# ESP32MainSchematice.net
KiCad netlist of a schematic drawn in Altium Designer
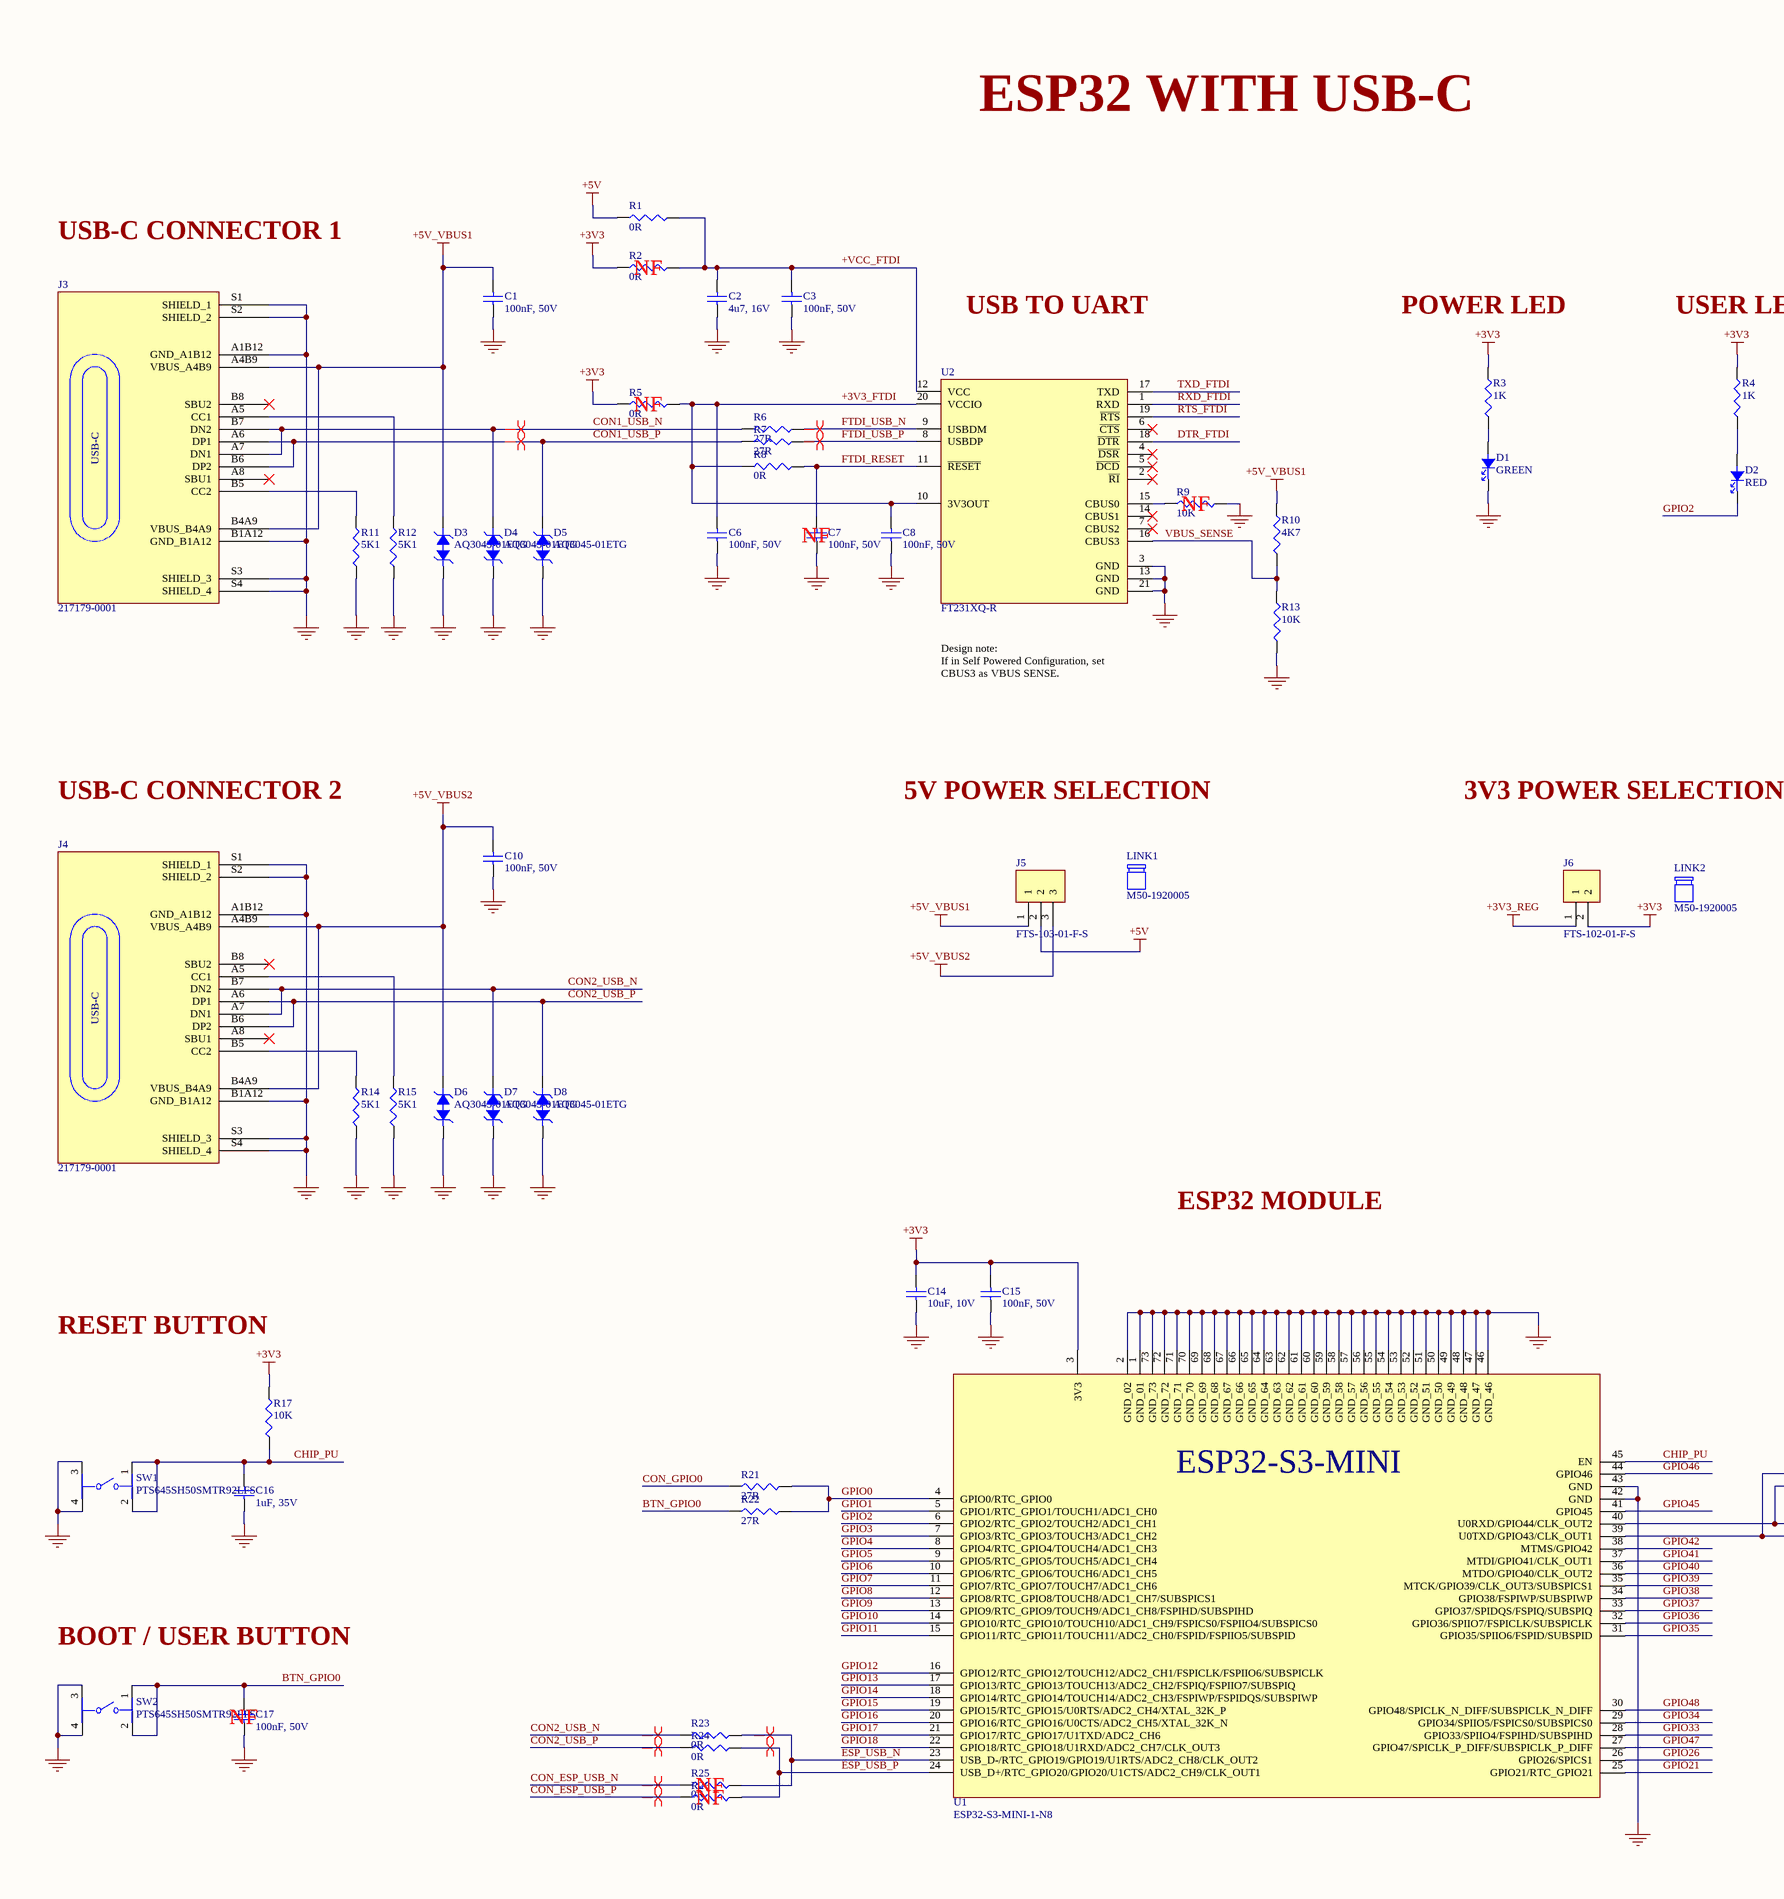
[diagram p0: ESP32MainSchematice.SchDoc, left]
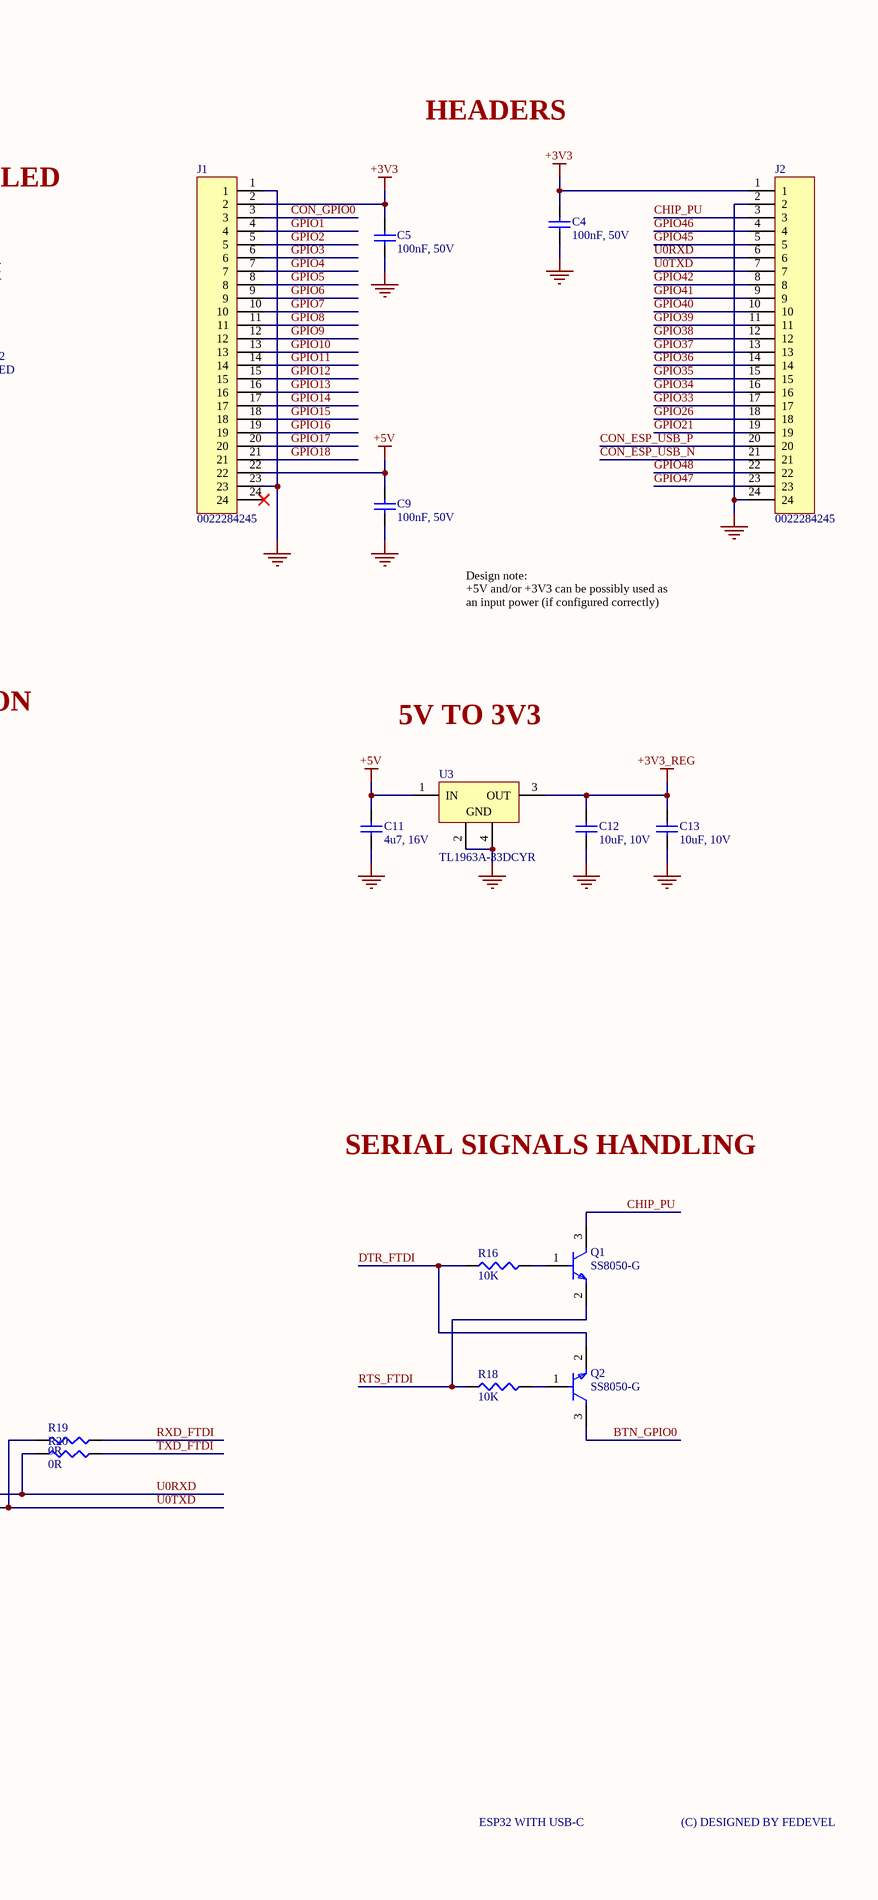
[diagram p1: ESP32MainSchematice.SchDoc, right]

(export (version "E")
  (design (tool "Eeschema 10.0.6"))
  (components
    (comp (ref "C1")
      (value "100nF, 50V")
      (footprint "CAPC1005X55N")
      (description "CAP CER 0.1UF 50V X7R 0402")
      (fields
        (field (name "MANUFACTURER") "Samsung")
        (field (name "MANUFACTURER PART NUMBER") "CL05B104KB54PNC")
      )
      (libsource (lib "Schlib") (part "CL05B104KB54PNC"))
    )
    (comp (ref "C2")
      (value "4u7, 16V")
      (footprint "CAPC1005X55N")
      (description "CAP CER 4.7UF 16V X5R 0402")
      (fields
        (field (name "MANUFACTURER") "Samsung")
        (field (name "MANUFACTURER PART NUMBER") "CL05A475MO5NUNC")
      )
      (libsource (lib "Schlib") (part "CL05A475MO5NUNC"))
    )
    (comp (ref "C3")
      (value "100nF, 50V")
      (footprint "CAPC1005X55N")
      (description "CAP CER 0.1UF 50V X7R 0402")
      (fields
        (field (name "MANUFACTURER") "Samsung")
        (field (name "MANUFACTURER PART NUMBER") "CL05B104KB54PNC")
      )
      (libsource (lib "Schlib") (part "CL05B104KB54PNC"))
    )
    (comp (ref "C4")
      (value "100nF, 50V")
      (footprint "CAPC1005X55N")
      (description "CAP CER 0.1UF 50V X7R 0402")
      (fields
        (field (name "MANUFACTURER") "Samsung")
        (field (name "MANUFACTURER PART NUMBER") "CL05B104KB54PNC")
      )
      (libsource (lib "Schlib") (part "CL05B104KB54PNC"))
    )
    (comp (ref "C5")
      (value "100nF, 50V")
      (footprint "CAPC1005X55N")
      (description "CAP CER 0.1UF 50V X7R 0402")
      (fields
        (field (name "MANUFACTURER") "Samsung")
        (field (name "MANUFACTURER PART NUMBER") "CL05B104KB54PNC")
      )
      (libsource (lib "Schlib") (part "CL05B104KB54PNC"))
    )
    (comp (ref "C6")
      (value "100nF, 50V")
      (footprint "CAPC1005X55N")
      (description "CAP CER 0.1UF 50V X7R 0402")
      (fields
        (field (name "MANUFACTURER") "Samsung")
        (field (name "MANUFACTURER PART NUMBER") "CL05B104KB54PNC")
      )
      (libsource (lib "Schlib") (part "CL05B104KB54PNC"))
    )
    (comp (ref "C7")
      (value "100nF, 50V")
      (footprint "CAPC1005X55N")
      (description "CAP CER 0.1UF 50V X7R 0402")
      (fields
        (field (name "MANUFACTURER") "Samsung")
        (field (name "MANUFACTURER PART NUMBER") "CL05B104KB54PNC")
      )
      (libsource (lib "Schlib") (part "CL05B104KB54PNC"))
    )
    (comp (ref "C8")
      (value "100nF, 50V")
      (footprint "CAPC1005X55N")
      (description "CAP CER 0.1UF 50V X7R 0402")
      (fields
        (field (name "MANUFACTURER") "Samsung")
        (field (name "MANUFACTURER PART NUMBER") "CL05B104KB54PNC")
      )
      (libsource (lib "Schlib") (part "CL05B104KB54PNC"))
    )
    (comp (ref "C9")
      (value "100nF, 50V")
      (footprint "CAPC1005X55N")
      (description "CAP CER 0.1UF 50V X7R 0402")
      (fields
        (field (name "MANUFACTURER") "Samsung")
        (field (name "MANUFACTURER PART NUMBER") "CL05B104KB54PNC")
      )
      (libsource (lib "Schlib") (part "CL05B104KB54PNC"))
    )
    (comp (ref "C10")
      (value "100nF, 50V")
      (footprint "CAPC1005X55N")
      (description "CAP CER 0.1UF 50V X7R 0402")
      (fields
        (field (name "MANUFACTURER") "Samsung")
        (field (name "MANUFACTURER PART NUMBER") "CL05B104KB54PNC")
      )
      (libsource (lib "Schlib") (part "CL05B104KB54PNC"))
    )
    (comp (ref "C11")
      (value "4u7, 16V")
      (footprint "CAPC1005X55N")
      (description "CAP CER 4.7UF 16V X5R 0402")
      (fields
        (field (name "MANUFACTURER") "Samsung")
        (field (name "MANUFACTURER PART NUMBER") "CL05A475MO5NUNC")
      )
      (libsource (lib "Schlib") (part "CL05A475MO5NUNC"))
    )
    (comp (ref "C12")
      (value "10uF, 10V")
      (footprint "CAPC1005X55N")
      (description "CAP CER 10UF 10V X5R 0402")
      (fields
        (field (name "MANUFACTURER") "Samsung")
        (field (name "MANUFACTURER PART NUMBER") "CL05A106MP8NUB8")
      )
      (libsource (lib "Schlib") (part "CL05A106MP8NUB8"))
    )
    (comp (ref "C13")
      (value "10uF, 10V")
      (footprint "CAPC1005X55N")
      (description "CAP CER 10UF 10V X5R 0402")
      (fields
        (field (name "MANUFACTURER") "Samsung")
        (field (name "MANUFACTURER PART NUMBER") "CL05A106MP8NUB8")
      )
      (libsource (lib "Schlib") (part "CL05A106MP8NUB8"))
    )
    (comp (ref "C14")
      (value "10uF, 10V")
      (footprint "CAPC1005X55N")
      (description "CAP CER 10UF 10V X5R 0402")
      (fields
        (field (name "MANUFACTURER") "Samsung")
        (field (name "MANUFACTURER PART NUMBER") "CL05A106MP8NUB8")
      )
      (libsource (lib "Schlib") (part "CL05A106MP8NUB8"))
    )
    (comp (ref "C15")
      (value "100nF, 50V")
      (footprint "CAPC1005X55N")
      (description "CAP CER 0.1UF 50V X7R 0402")
      (fields
        (field (name "MANUFACTURER") "Samsung")
        (field (name "MANUFACTURER PART NUMBER") "CL05B104KB54PNC")
      )
      (libsource (lib "Schlib") (part "CL05B104KB54PNC"))
    )
    (comp (ref "C16")
      (value "1uF, 35V")
      (footprint "CAPC1005X55N")
      (description "CAP CER 1UF 35V X5R 0402")
      (fields
        (field (name "MANUFACTURER") "Samsung")
        (field (name "MANUFACTURER PART NUMBER") "CL05A105KL5NRNC")
      )
      (libsource (lib "Schlib") (part "CL05A105KL5NRNC"))
    )
    (comp (ref "C17")
      (value "100nF, 50V")
      (footprint "CAPC1005X55N")
      (description "CAP CER 0.1UF 50V X7R 0402")
      (fields
        (field (name "MANUFACTURER") "Samsung")
        (field (name "MANUFACTURER PART NUMBER") "CL05B104KB54PNC")
      )
      (libsource (lib "Schlib") (part "CL05B104KB54PNC"))
    )
    (comp (ref "D1")
      (value "GREEN")
      (footprint "LED0402G")
      (description "LED YLW-GRN 0402 SMD")
      (fields
        (field (name "MANUFACTURER") "Vishay")
        (field (name "MANUFACTURER PART NUMBER") "VLMG1500-GS08")
      )
      (libsource (lib "Schlib") (part "VLMG1500-GS08"))
    )
    (comp (ref "D2")
      (value "RED")
      (footprint "LED0402R")
      (description "LED RED 0402 SMD")
      (fields
        (field (name "MANUFACTURER") "Vishay")
        (field (name "MANUFACTURER PART NUMBER") "VLMS1500-GS08")
      )
      (libsource (lib "Schlib") (part "VLMS1500-GS08"))
    )
    (comp (ref "D3")
      (value "AQ3045-01ETG")
      (footprint "SOD882")
      (description "TVS DIODE 5.3VWM 12VC SOD882")
      (fields (field (name "MANUFACTURER") "Littelfuse") (field (name "LCSC PART NUMBER") "C3710326"))
      (libsource (lib "Schlib") (part "AQ3045-01ETG"))
    )
    (comp (ref "D4")
      (value "AQ3045-01ETG")
      (footprint "SOD882")
      (description "TVS DIODE 5.3VWM 12VC SOD882")
      (fields (field (name "MANUFACTURER") "Littelfuse") (field (name "LCSC PART NUMBER") "C3710326"))
      (libsource (lib "Schlib") (part "AQ3045-01ETG"))
    )
    (comp (ref "D5")
      (value "AQ3045-01ETG")
      (footprint "SOD882")
      (description "TVS DIODE 5.3VWM 12VC SOD882")
      (fields (field (name "MANUFACTURER") "Littelfuse") (field (name "LCSC PART NUMBER") "C3710326"))
      (libsource (lib "Schlib") (part "AQ3045-01ETG"))
    )
    (comp (ref "D6")
      (value "AQ3045-01ETG")
      (footprint "SOD882")
      (description "TVS DIODE 5.3VWM 12VC SOD882")
      (fields (field (name "MANUFACTURER") "Littelfuse") (field (name "LCSC PART NUMBER") "C3710326"))
      (libsource (lib "Schlib") (part "AQ3045-01ETG"))
    )
    (comp (ref "D7")
      (value "AQ3045-01ETG")
      (footprint "SOD882")
      (description "TVS DIODE 5.3VWM 12VC SOD882")
      (fields (field (name "MANUFACTURER") "Littelfuse") (field (name "LCSC PART NUMBER") "C3710326"))
      (libsource (lib "Schlib") (part "AQ3045-01ETG"))
    )
    (comp (ref "D8")
      (value "AQ3045-01ETG")
      (footprint "SOD882")
      (description "TVS DIODE 5.3VWM 12VC SOD882")
      (fields (field (name "MANUFACTURER") "Littelfuse") (field (name "LCSC PART NUMBER") "C3710326"))
      (libsource (lib "Schlib") (part "AQ3045-01ETG"))
    )
    (comp (ref "J1")
      (value "0022284245")
      (footprint "HDR_1X24_2.54MM")
      (description "CONN HEADER VERT 24POS 2.54MM")
      (fields (field (name "MANUFACTURER") "Molex") (field (name "LCSC PART NUMBER") "C7145888"))
      (libsource (lib "Schlib") (part "0022284245"))
    )
    (comp (ref "J2")
      (value "0022284245")
      (footprint "HDR_1X24_2.54MM")
      (description "CONN HEADER VERT 24POS 2.54MM")
      (fields (field (name "MANUFACTURER") "Molex") (field (name "LCSC PART NUMBER") "C7145888"))
      (libsource (lib "") (part "0022284245_1"))
    )
    (comp (ref "J3")
      (value "217179-0001")
      (footprint "FP-2171790001-MFG")
      (description "CONN RCP USB2.0 TYP C 24P SMD RA")
      (fields (field (name "MANUFACTURER") "Molex") (field (name "LCSC PART NUMBER") "C3197684"))
      (libsource (lib "Schlib") (part "217179-0001"))
    )
    (comp (ref "J4")
      (value "217179-0001")
      (footprint "FP-2171790001-MFG")
      (description "CONN RCP USB2.0 TYP C 24P SMD RA")
      (fields (field (name "MANUFACTURER") "Molex") (field (name "LCSC PART NUMBER") "C3197684"))
      (libsource (lib "Schlib") (part "217179-0001"))
    )
    (comp (ref "J5")
      (value "FTS-103-01-F-S")
      (footprint "HDR_1X3_1.27MM")
      (description "CONN HEADER VERT 3POS 1.27MM")
      (fields (field (name "MANUFACTURER") "Samtec") (field (name "LCSC PART NUMBER") "C3333578"))
      (libsource (lib "Schlib") (part "FTS-103-01-F-S"))
    )
    (comp (ref "J6")
      (value "FTS-102-01-F-S")
      (footprint "HDR_1X2_1.27MM")
      (description "CONN HEADER VERT 2POS 1.27MM")
      (fields (field (name "MANUFACTURER") "Samtec") (field (name "LCSC PART NUMBER") "C6045317"))
      (libsource (lib "Schlib") (part "FTS-102-01-F-S"))
    )
    (comp (ref "LINK1")
      (value "M50-1920005")
      (description "CONN SHUNT 1.27MM RED")
      (fields (field (name "MANUFACTURER") "Harwin") (field (name "LCSC PART NUMBER") "C6985646"))
      (libsource (lib "Schlib") (part "M50-1920005"))
    )
    (comp (ref "LINK2")
      (value "M50-1920005")
      (description "CONN SHUNT 1.27MM RED")
      (fields (field (name "MANUFACTURER") "Harwin") (field (name "LCSC PART NUMBER") "C6985646"))
      (libsource (lib "Schlib") (part "M50-1920005"))
    )
    (comp (ref "Q1")
      (value "SS8050-G")
      (footprint "FP-SS8050-G-IPC_B")
      (description "TRANS NPN 25V 1.5A SOT23-3")
      (fields (field (name "MANUFACTURER") "Comchip") (field (name "LCSC PART NUMBER") "C164886"))
      (libsource (lib "Schlib") (part "SS8050-G"))
    )
    (comp (ref "Q2")
      (value "SS8050-G")
      (footprint "FP-SS8050-G-IPC_B")
      (description "TRANS NPN 25V 1.5A SOT23-3")
      (fields (field (name "MANUFACTURER") "Comchip") (field (name "LCSC PART NUMBER") "C164886"))
      (libsource (lib "Schlib") (part "SS8050-G"))
    )
    (comp (ref "R1")
      (value "0R")
      (footprint "RESC1005X37N")
      (description "RES 0 OHM JUMPER 1/16W 0402")
      (fields
        (field (name "MANUFACTURER") "Yageo")
        (field (name "MANUFACTURER PART NUMBER") "RC0402JR-070RL")
      )
      (libsource (lib "Schlib") (part "RC0402JR-070RL"))
    )
    (comp (ref "R2")
      (value "0R")
      (footprint "RESC1005X37N")
      (description "RES 0 OHM JUMPER 1/16W 0402")
      (fields
        (field (name "MANUFACTURER") "Yageo")
        (field (name "MANUFACTURER PART NUMBER") "RC0402JR-070RL")
      )
      (libsource (lib "Schlib") (part "RC0402JR-070RL"))
    )
    (comp (ref "R3")
      (value "1K")
      (footprint "RESC1005X37N")
      (description "RES 1K OHM 1% 1/16W 0402")
      (fields
        (field (name "MANUFACTURER") "Yageo")
        (field (name "MANUFACTURER PART NUMBER") "RC0402FR-071KL")
      )
      (libsource (lib "Schlib") (part "RC0402FR-071KL"))
    )
    (comp (ref "R4")
      (value "1K")
      (footprint "RESC1005X37N")
      (description "RES 1K OHM 1% 1/16W 0402")
      (fields
        (field (name "MANUFACTURER") "Yageo")
        (field (name "MANUFACTURER PART NUMBER") "RC0402FR-071KL")
      )
      (libsource (lib "Schlib") (part "RC0402FR-071KL"))
    )
    (comp (ref "R5")
      (value "0R")
      (footprint "RESC1005X37N")
      (description "RES 0 OHM JUMPER 1/16W 0402")
      (fields
        (field (name "MANUFACTURER") "Yageo")
        (field (name "MANUFACTURER PART NUMBER") "RC0402JR-070RL")
      )
      (libsource (lib "Schlib") (part "RC0402JR-070RL"))
    )
    (comp (ref "R6")
      (value "27R")
      (footprint "RESC1005X37N")
      (description "RES 27 OHM 1% 1/16W 0402")
      (fields
        (field (name "MANUFACTURER") "Yageo")
        (field (name "MANUFACTURER PART NUMBER") "RC0402FR-0727RL")
      )
      (libsource (lib "Schlib") (part "RC0402FR-0727RL"))
    )
    (comp (ref "R7")
      (value "27R")
      (footprint "RESC1005X37N")
      (description "RES 27 OHM 1% 1/16W 0402")
      (fields
        (field (name "MANUFACTURER") "Yageo")
        (field (name "MANUFACTURER PART NUMBER") "RC0402FR-0727RL")
      )
      (libsource (lib "Schlib") (part "RC0402FR-0727RL"))
    )
    (comp (ref "R8")
      (value "0R")
      (footprint "RESC1005X37N")
      (description "RES 0 OHM JUMPER 1/16W 0402")
      (fields
        (field (name "MANUFACTURER") "Yageo")
        (field (name "MANUFACTURER PART NUMBER") "RC0402JR-070RL")
      )
      (libsource (lib "Schlib") (part "RC0402JR-070RL"))
    )
    (comp (ref "R9")
      (value "10K")
      (footprint "RESC1005X37N")
      (description "RES SMD 10K OHM 1% 1/16W 0402")
      (fields
        (field (name "MANUFACTURER") "Yageo")
        (field (name "MANUFACTURER PART NUMBER") "AC0402FR-0710KL")
      )
      (libsource (lib "Schlib") (part "AC0402FR-0710KL"))
    )
    (comp (ref "R10")
      (value "4K7")
      (footprint "RESC1005X37N")
      (description "RES 4.7K OHM 1% 1/16W 0402")
      (fields
        (field (name "MANUFACTURER") "Yageo")
        (field (name "MANUFACTURER PART NUMBER") "RC0402FR-074K7L")
      )
      (libsource (lib "Schlib") (part "RC0402FR-074K7L"))
    )
    (comp (ref "R11")
      (value "5K1")
      (footprint "RESC1005X37N")
      (description "RES SMD 5.1K OHM 1% 1/16W 0402")
      (fields
        (field (name "MANUFACTURER") "Yageo")
        (field (name "MANUFACTURER PART NUMBER") "AC0402FR-075K1L")
      )
      (libsource (lib "Schlib") (part "AC0402FR-075K1L"))
    )
    (comp (ref "R12")
      (value "5K1")
      (footprint "RESC1005X37N")
      (description "RES SMD 5.1K OHM 1% 1/16W 0402")
      (fields
        (field (name "MANUFACTURER") "Yageo")
        (field (name "MANUFACTURER PART NUMBER") "AC0402FR-075K1L")
      )
      (libsource (lib "Schlib") (part "AC0402FR-075K1L"))
    )
    (comp (ref "R13")
      (value "10K")
      (footprint "RESC1005X37N")
      (description "RES SMD 10K OHM 1% 1/16W 0402")
      (fields
        (field (name "MANUFACTURER") "Yageo")
        (field (name "MANUFACTURER PART NUMBER") "AC0402FR-0710KL")
      )
      (libsource (lib "Schlib") (part "AC0402FR-0710KL"))
    )
    (comp (ref "R14")
      (value "5K1")
      (footprint "RESC1005X37N")
      (description "RES SMD 5.1K OHM 1% 1/16W 0402")
      (fields
        (field (name "MANUFACTURER") "Yageo")
        (field (name "MANUFACTURER PART NUMBER") "AC0402FR-075K1L")
      )
      (libsource (lib "Schlib") (part "AC0402FR-075K1L"))
    )
    (comp (ref "R15")
      (value "5K1")
      (footprint "RESC1005X37N")
      (description "RES SMD 5.1K OHM 1% 1/16W 0402")
      (fields
        (field (name "MANUFACTURER") "Yageo")
        (field (name "MANUFACTURER PART NUMBER") "AC0402FR-075K1L")
      )
      (libsource (lib "Schlib") (part "AC0402FR-075K1L"))
    )
    (comp (ref "R16")
      (value "10K")
      (footprint "RESC1005X37N")
      (description "RES SMD 10K OHM 1% 1/16W 0402")
      (fields
        (field (name "MANUFACTURER") "Yageo")
        (field (name "MANUFACTURER PART NUMBER") "AC0402FR-0710KL")
      )
      (libsource (lib "Schlib") (part "AC0402FR-0710KL"))
    )
    (comp (ref "R17")
      (value "10K")
      (footprint "RESC1005X37N")
      (description "RES SMD 10K OHM 1% 1/16W 0402")
      (fields
        (field (name "MANUFACTURER") "Yageo")
        (field (name "MANUFACTURER PART NUMBER") "AC0402FR-0710KL")
      )
      (libsource (lib "Schlib") (part "AC0402FR-0710KL"))
    )
    (comp (ref "R18")
      (value "10K")
      (footprint "RESC1005X37N")
      (description "RES SMD 10K OHM 1% 1/16W 0402")
      (fields
        (field (name "MANUFACTURER") "Yageo")
        (field (name "MANUFACTURER PART NUMBER") "AC0402FR-0710KL")
      )
      (libsource (lib "Schlib") (part "AC0402FR-0710KL"))
    )
    (comp (ref "R19")
      (value "0R")
      (footprint "RESC1005X37N")
      (description "RES 0 OHM JUMPER 1/16W 0402")
      (fields
        (field (name "MANUFACTURER") "Yageo")
        (field (name "MANUFACTURER PART NUMBER") "RC0402JR-070RL")
      )
      (libsource (lib "Schlib") (part "RC0402JR-070RL"))
    )
    (comp (ref "R20")
      (value "0R")
      (footprint "RESC1005X37N")
      (description "RES 0 OHM JUMPER 1/16W 0402")
      (fields
        (field (name "MANUFACTURER") "Yageo")
        (field (name "MANUFACTURER PART NUMBER") "RC0402JR-070RL")
      )
      (libsource (lib "Schlib") (part "RC0402JR-070RL"))
    )
    (comp (ref "R21")
      (value "27R")
      (footprint "RESC1005X37N")
      (description "RES 27 OHM 1% 1/16W 0402")
      (fields
        (field (name "MANUFACTURER") "Yageo")
        (field (name "MANUFACTURER PART NUMBER") "RC0402FR-0727RL")
      )
      (libsource (lib "Schlib") (part "RC0402FR-0727RL"))
    )
    (comp (ref "R22")
      (value "27R")
      (footprint "RESC1005X37N")
      (description "RES 27 OHM 1% 1/16W 0402")
      (fields
        (field (name "MANUFACTURER") "Yageo")
        (field (name "MANUFACTURER PART NUMBER") "RC0402FR-0727RL")
      )
      (libsource (lib "Schlib") (part "RC0402FR-0727RL"))
    )
    (comp (ref "R23")
      (value "0R")
      (footprint "RESC1005X37N")
      (description "RES 0 OHM JUMPER 1/16W 0402")
      (fields
        (field (name "MANUFACTURER") "Yageo")
        (field (name "MANUFACTURER PART NUMBER") "RC0402JR-070RL")
      )
      (libsource (lib "Schlib") (part "RC0402JR-070RL"))
    )
    (comp (ref "R24")
      (value "0R")
      (footprint "RESC1005X37N")
      (description "RES 0 OHM JUMPER 1/16W 0402")
      (fields
        (field (name "MANUFACTURER") "Yageo")
        (field (name "MANUFACTURER PART NUMBER") "RC0402JR-070RL")
      )
      (libsource (lib "Schlib") (part "RC0402JR-070RL"))
    )
    (comp (ref "R25")
      (value "0R")
      (footprint "RESC1005X37N")
      (description "RES 0 OHM JUMPER 1/16W 0402")
      (fields
        (field (name "MANUFACTURER") "Yageo")
        (field (name "MANUFACTURER PART NUMBER") "RC0402JR-070RL")
      )
      (libsource (lib "Schlib") (part "RC0402JR-070RL"))
    )
    (comp (ref "R26")
      (value "0R")
      (footprint "RESC1005X37N")
      (description "RES 0 OHM JUMPER 1/16W 0402")
      (fields
        (field (name "MANUFACTURER") "Yageo")
        (field (name "MANUFACTURER PART NUMBER") "RC0402JR-070RL")
      )
      (libsource (lib "Schlib") (part "RC0402JR-070RL"))
    )
    (comp (ref "SW1")
      (value "PTS645SH50SMTR92LFS")
      (footprint "FP-PTS645SH50SMTR92LFS-MFG")
      (description "SWITCH TACTILE SPST-NO 0.05A 12V")
      (fields (field (name "MANUFACTURER") "ITT C&K") (field (name "LCSC PART NUMBER") "C221869"))
      (libsource (lib "Schlib") (part "PTS645SH50SMTR92LFS"))
    )
    (comp (ref "SW2")
      (value "PTS645SH50SMTR92LFS")
      (footprint "FP-PTS645SH50SMTR92LFS-MFG")
      (description "SWITCH TACTILE SPST-NO 0.05A 12V")
      (fields (field (name "MANUFACTURER") "ITT C&K") (field (name "LCSC PART NUMBER") "C221869"))
      (libsource (lib "Schlib") (part "PTS645SH50SMTR92LFS"))
    )
    (comp (ref "U1")
      (value "ESP32-S3-MINI-1-N8")
      (footprint "XCVR_ESP32-S3-MINI-1-N8")
      (description "SMD Module, ESP32-S3FN8, 8 mb Sp")
      (fields (field (name "MANUFACTURER") "Espressif Systems") (field (name "LCSC PART NUMBER") "C2913206"))
      (libsource (lib "Schlib") (part "ESP32-S3-MINI-1-N8"))
    )
    (comp (ref "U2")
      (value "FT231XQ-R")
      (footprint "FP-QFN-20-IPC_B")
      (description "IC USB SERIAL FULL UART 20QFN")
      (fields (field (name "MANUFACTURER") "FTDI") (field (name "LCSC PART NUMBER") "C132159"))
      (libsource (lib "Schlib") (part "FT231XQ-R"))
    )
    (comp (ref "U3")
      (value "TL1963A-33DCYR")
      (footprint "DCY0004A_N")
      (description "IC REG LINEAR 3.3V 1.5A SOT223-4")
      (fields (field (name "MANUFACTURER") "Texas Instruments") (field (name "LCSC PART NUMBER") "C181262"))
      (libsource (lib "Schlib") (part "TL1963A-33DCYR"))
    )
  )
  (nets
    (net (code "1") (name "+3V3") (class "Default")
      (node (ref "C14") (pin "2") (pinfunction "2_2") (pintype "passive"))
      (node (ref "C15") (pin "2") (pinfunction "2_2") (pintype "passive"))
      (node (ref "C4") (pin "2") (pinfunction "2_2") (pintype "passive"))
      (node (ref "C5") (pin "2") (pinfunction "2_2") (pintype "passive"))
      (node (ref "J1") (pin "2") (pinfunction "2_2") (pintype "passive"))
      (node (ref "J2") (pin "1") (pinfunction "1_1") (pintype "passive"))
      (node (ref "J6") (pin "2") (pinfunction "2_2") (pintype "passive"))
      (node (ref "R17") (pin "2") (pinfunction "2_2") (pintype "passive"))
      (node (ref "R2") (pin "1") (pinfunction "1_1") (pintype "passive"))
      (node (ref "R3") (pin "2") (pinfunction "2_2") (pintype "passive"))
      (node (ref "R4") (pin "2") (pinfunction "2_2") (pintype "passive"))
      (node (ref "R5") (pin "1") (pinfunction "1_1") (pintype "passive"))
      (node (ref "U1") (pin "3") (pinfunction "3V3_3") (pintype "passive"))
    )
    (net (code "2") (name "+3V3_REG") (class "Default")
      (node (ref "C12") (pin "2") (pinfunction "2_2") (pintype "passive"))
      (node (ref "C13") (pin "2") (pinfunction "2_2") (pintype "passive"))
      (node (ref "J6") (pin "1") (pinfunction "1_1") (pintype "passive"))
      (node (ref "U3") (pin "3") (pinfunction "OUT_3") (pintype "power_in"))
    )
    (net (code "3") (name "+5V") (class "Default")
      (node (ref "C11") (pin "2") (pinfunction "2_2") (pintype "passive"))
      (node (ref "C9") (pin "2") (pinfunction "2_2") (pintype "passive"))
      (node (ref "J1") (pin "22") (pinfunction "22_22") (pintype "passive"))
      (node (ref "J5") (pin "2") (pinfunction "2_2") (pintype "passive"))
      (node (ref "R1") (pin "1") (pinfunction "1_1") (pintype "passive"))
      (node (ref "U3") (pin "1") (pinfunction "IN_1") (pintype "power_in"))
    )
    (net (code "4") (name "+5V_VBUS1") (class "Default")
      (node (ref "C1") (pin "2") (pinfunction "2_2") (pintype "passive"))
      (node (ref "D3") (pin "2") (pinfunction "2_2") (pintype "passive"))
      (node (ref "J3") (pin "A4B9") (pinfunction "VBUS_A4B9_A4B9") (pintype "passive"))
      (node (ref "J3") (pin "B4A9") (pinfunction "VBUS_B4A9_B4A9") (pintype "passive"))
      (node (ref "J5") (pin "1") (pinfunction "1_1") (pintype "passive"))
      (node (ref "R10") (pin "2") (pinfunction "2_2") (pintype "passive"))
    )
    (net (code "5") (name "+5V_VBUS2") (class "Default")
      (node (ref "C10") (pin "2") (pinfunction "2_2") (pintype "passive"))
      (node (ref "D6") (pin "2") (pinfunction "2_2") (pintype "passive"))
      (node (ref "J4") (pin "A4B9") (pinfunction "VBUS_A4B9_A4B9") (pintype "passive"))
      (node (ref "J4") (pin "B4A9") (pinfunction "VBUS_B4A9_B4A9") (pintype "passive"))
      (node (ref "J5") (pin "3") (pinfunction "3_3") (pintype "passive"))
    )
    (net (code "6") (name "/+3V3_FTDI") (class "Default")
      (node (ref "C6") (pin "2") (pinfunction "2_2") (pintype "passive"))
      (node (ref "C8") (pin "2") (pinfunction "2_2") (pintype "passive"))
      (node (ref "R5") (pin "2") (pinfunction "2_2") (pintype "passive"))
      (node (ref "R8") (pin "1") (pinfunction "1_1") (pintype "passive"))
      (node (ref "U2") (pin "10") (pinfunction "3V3OUT_10") (pintype "passive"))
      (node (ref "U2") (pin "20") (pinfunction "VCCIO_20") (pintype "passive"))
    )
    (net (code "7") (name "/+VCC_FTDI") (class "Default")
      (node (ref "C2") (pin "2") (pinfunction "2_2") (pintype "passive"))
      (node (ref "C3") (pin "2") (pinfunction "2_2") (pintype "passive"))
      (node (ref "R1") (pin "2") (pinfunction "2_2") (pintype "passive"))
      (node (ref "R2") (pin "2") (pinfunction "2_2") (pintype "passive"))
      (node (ref "U2") (pin "12") (pinfunction "VCC_12") (pintype "passive"))
    )
    (net (code "8") (name "/BTN_GPIO0") (class "Default")
      (node (ref "C17") (pin "2") (pinfunction "2_2") (pintype "passive"))
      (node (ref "Q2") (pin "3") (pinfunction "C_3") (pintype "passive"))
      (node (ref "R22") (pin "1") (pinfunction "1_1") (pintype "passive"))
      (node (ref "SW2") (pin "1") (pinfunction "1_1") (pintype "passive"))
      (node (ref "SW2") (pin "2") (pinfunction "2_2") (pintype "passive"))
    )
    (net (code "9") (name "/CHIP_PU") (class "Default")
      (node (ref "C16") (pin "2") (pinfunction "2_2") (pintype "passive"))
      (node (ref "J2") (pin "3") (pinfunction "3_3") (pintype "passive"))
      (node (ref "Q1") (pin "3") (pinfunction "C_3") (pintype "passive"))
      (node (ref "R17") (pin "1") (pinfunction "1_1") (pintype "passive"))
      (node (ref "SW1") (pin "1") (pinfunction "1_1") (pintype "passive"))
      (node (ref "SW1") (pin "2") (pinfunction "2_2") (pintype "passive"))
      (node (ref "U1") (pin "45") (pinfunction "EN_45") (pintype "passive"))
    )
    (net (code "10") (name "/CON1_USB_N") (class "Default")
      (node (ref "D4") (pin "2") (pinfunction "2_2") (pintype "passive"))
      (node (ref "J3") (pin "A7") (pinfunction "DN1_A7") (pintype "passive"))
      (node (ref "J3") (pin "B7") (pinfunction "DN2_B7") (pintype "passive"))
      (node (ref "R6") (pin "1") (pinfunction "1_1") (pintype "passive"))
    )
    (net (code "11") (name "/CON1_USB_P") (class "Default")
      (node (ref "D5") (pin "2") (pinfunction "2_2") (pintype "passive"))
      (node (ref "J3") (pin "A6") (pinfunction "DP1_A6") (pintype "passive"))
      (node (ref "J3") (pin "B6") (pinfunction "DP2_B6") (pintype "passive"))
      (node (ref "R7") (pin "1") (pinfunction "1_1") (pintype "passive"))
    )
    (net (code "12") (name "/CON2_USB_N") (class "Default")
      (node (ref "D7") (pin "2") (pinfunction "2_2") (pintype "passive"))
      (node (ref "J4") (pin "A7") (pinfunction "DN1_A7") (pintype "passive"))
      (node (ref "J4") (pin "B7") (pinfunction "DN2_B7") (pintype "passive"))
      (node (ref "R23") (pin "1") (pinfunction "1_1") (pintype "passive"))
    )
    (net (code "13") (name "/CON2_USB_P") (class "Default")
      (node (ref "D8") (pin "2") (pinfunction "2_2") (pintype "passive"))
      (node (ref "J4") (pin "A6") (pinfunction "DP1_A6") (pintype "passive"))
      (node (ref "J4") (pin "B6") (pinfunction "DP2_B6") (pintype "passive"))
      (node (ref "R24") (pin "1") (pinfunction "1_1") (pintype "passive"))
    )
    (net (code "14") (name "/CON_ESP_USB_N") (class "Default")
      (node (ref "J2") (pin "21") (pinfunction "21_21") (pintype "passive"))
      (node (ref "R25") (pin "1") (pinfunction "1_1") (pintype "passive"))
    )
    (net (code "15") (name "/CON_ESP_USB_P") (class "Default")
      (node (ref "J2") (pin "20") (pinfunction "20_20") (pintype "passive"))
      (node (ref "R26") (pin "1") (pinfunction "1_1") (pintype "passive"))
    )
    (net (code "16") (name "/CON_GPIO0") (class "Default")
      (node (ref "J1") (pin "3") (pinfunction "3_3") (pintype "passive"))
      (node (ref "R21") (pin "1") (pinfunction "1_1") (pintype "passive"))
    )
    (net (code "17") (name "/DTR_FTDI") (class "Default")
      (node (ref "Q2") (pin "2") (pinfunction "E_2") (pintype "passive"))
      (node (ref "R16") (pin "1") (pinfunction "1_1") (pintype "passive"))
      (node (ref "U2") (pin "18") (pinfunction "~{DTR}_18") (pintype "passive"))
    )
    (net (code "18") (name "/ESP_USB_N") (class "Default")
      (node (ref "R23") (pin "2") (pinfunction "2_2") (pintype "passive"))
      (node (ref "R25") (pin "2") (pinfunction "2_2") (pintype "passive"))
      (node (ref "U1") (pin "23") (pinfunction "USB_D-/RTC_GPIO19/GPIO19/U1RTS/ADC2_CH8/CLK_OUT2_23") (pintype "passive"))
    )
    (net (code "19") (name "/ESP_USB_P") (class "Default")
      (node (ref "R24") (pin "2") (pinfunction "2_2") (pintype "passive"))
      (node (ref "R26") (pin "2") (pinfunction "2_2") (pintype "passive"))
      (node (ref "U1") (pin "24") (pinfunction "USB_D+/RTC_GPIO20/GPIO20/U1CTS/ADC2_CH9/CLK_OUT1_24") (pintype "passive"))
    )
    (net (code "20") (name "/FTDI_RESET") (class "Default")
      (node (ref "C7") (pin "2") (pinfunction "2_2") (pintype "passive"))
      (node (ref "R8") (pin "2") (pinfunction "2_2") (pintype "passive"))
      (node (ref "U2") (pin "11") (pinfunction "~{RESET}_11") (pintype "passive"))
    )
    (net (code "21") (name "/FTDI_USB_N") (class "Default")
      (node (ref "R6") (pin "2") (pinfunction "2_2") (pintype "passive"))
      (node (ref "U2") (pin "9") (pinfunction "USBDM_9") (pintype "passive"))
    )
    (net (code "22") (name "/FTDI_USB_P") (class "Default")
      (node (ref "R7") (pin "2") (pinfunction "2_2") (pintype "passive"))
      (node (ref "U2") (pin "8") (pinfunction "USBDP_8") (pintype "passive"))
    )
    (net (code "23") (name "/GPIO0") (class "Default")
      (node (ref "R21") (pin "2") (pinfunction "2_2") (pintype "passive"))
      (node (ref "R22") (pin "2") (pinfunction "2_2") (pintype "passive"))
      (node (ref "U1") (pin "4") (pinfunction "GPIO0/RTC_GPIO0_4") (pintype "passive"))
    )
    (net (code "24") (name "/GPIO1") (class "Default")
      (node (ref "J1") (pin "4") (pinfunction "4_4") (pintype "passive"))
      (node (ref "U1") (pin "5") (pinfunction "GPIO1/RTC_GPIO1/TOUCH1/ADC1_CH0_5") (pintype "passive"))
    )
    (net (code "25") (name "/GPIO2") (class "Default")
      (node (ref "D2") (pin "1") (pinfunction "1_1") (pintype "passive"))
      (node (ref "J1") (pin "5") (pinfunction "5_5") (pintype "passive"))
      (node (ref "U1") (pin "6") (pinfunction "GPIO2/RTC_GPIO2/TOUCH2/ADC1_CH1_6") (pintype "passive"))
    )
    (net (code "26") (name "/GPIO3") (class "Default")
      (node (ref "J1") (pin "6") (pinfunction "6_6") (pintype "passive"))
      (node (ref "U1") (pin "7") (pinfunction "GPIO3/RTC_GPIO3/TOUCH3/ADC1_CH2_7") (pintype "passive"))
    )
    (net (code "27") (name "/GPIO4") (class "Default")
      (node (ref "J1") (pin "7") (pinfunction "7_7") (pintype "passive"))
      (node (ref "U1") (pin "8") (pinfunction "GPIO4/RTC_GPIO4/TOUCH4/ADC1_CH3_8") (pintype "passive"))
    )
    (net (code "28") (name "/GPIO5") (class "Default")
      (node (ref "J1") (pin "8") (pinfunction "8_8") (pintype "passive"))
      (node (ref "U1") (pin "9") (pinfunction "GPIO5/RTC_GPIO5/TOUCH5/ADC1_CH4_9") (pintype "passive"))
    )
    (net (code "29") (name "/GPIO6") (class "Default")
      (node (ref "J1") (pin "9") (pinfunction "9_9") (pintype "passive"))
      (node (ref "U1") (pin "10") (pinfunction "GPIO6/RTC_GPIO6/TOUCH6/ADC1_CH5_10") (pintype "passive"))
    )
    (net (code "30") (name "/GPIO7") (class "Default")
      (node (ref "J1") (pin "10") (pinfunction "10_10") (pintype "passive"))
      (node (ref "U1") (pin "11") (pinfunction "GPIO7/RTC_GPIO7/TOUCH7/ADC1_CH6_11") (pintype "passive"))
    )
    (net (code "31") (name "/GPIO8") (class "Default")
      (node (ref "J1") (pin "11") (pinfunction "11_11") (pintype "passive"))
      (node (ref "U1") (pin "12") (pinfunction "GPIO8/RTC_GPIO8/TOUCH8/ADC1_CH7/SUBSPICS1_12") (pintype "passive"))
    )
    (net (code "32") (name "/GPIO9") (class "Default")
      (node (ref "J1") (pin "12") (pinfunction "12_12") (pintype "passive"))
      (node (ref "U1") (pin "13") (pinfunction "GPIO9/RTC_GPIO9/TOUCH9/ADC1_CH8/FSPIHD/SUBSPIHD_13") (pintype "passive"))
    )
    (net (code "33") (name "/GPIO10") (class "Default")
      (node (ref "J1") (pin "13") (pinfunction "13_13") (pintype "passive"))
      (node (ref "U1") (pin "14") (pinfunction "GPIO10/RTC_GPIO10/TOUCH10/ADC1_CH9/FSPICS0/FSPIIO4/SUBSPICS0_14") (pintype "passive"))
    )
    (net (code "34") (name "/GPIO11") (class "Default")
      (node (ref "J1") (pin "14") (pinfunction "14_14") (pintype "passive"))
      (node (ref "U1") (pin "15") (pinfunction "GPIO11/RTC_GPIO11/TOUCH11/ADC2_CH0/FSPID/FSPIIO5/SUBSPID_15") (pintype "passive"))
    )
    (net (code "35") (name "/GPIO12") (class "Default")
      (node (ref "J1") (pin "15") (pinfunction "15_15") (pintype "passive"))
      (node (ref "U1") (pin "16") (pinfunction "GPIO12/RTC_GPIO12/TOUCH12/ADC2_CH1/FSPICLK/FSPIIO6/SUBSPICLK_16") (pintype "passive"))
    )
    (net (code "36") (name "/GPIO13") (class "Default")
      (node (ref "J1") (pin "16") (pinfunction "16_16") (pintype "passive"))
      (node (ref "U1") (pin "17") (pinfunction "GPIO13/RTC_GPIO13/TOUCH13/ADC2_CH2/FSPIQ/FSPIIO7/SUBSPIQ_17") (pintype "passive"))
    )
    (net (code "37") (name "/GPIO14") (class "Default")
      (node (ref "J1") (pin "17") (pinfunction "17_17") (pintype "passive"))
      (node (ref "U1") (pin "18") (pinfunction "GPIO14/RTC_GPIO14/TOUCH14/ADC2_CH3/FSPIWP/FSPIDQS/SUBSPIWP_18") (pintype "passive"))
    )
    (net (code "38") (name "/GPIO15") (class "Default")
      (node (ref "J1") (pin "18") (pinfunction "18_18") (pintype "passive"))
      (node (ref "U1") (pin "19") (pinfunction "GPIO15/RTC_GPIO15/U0RTS/ADC2_CH4/XTAL_32K_P_19") (pintype "passive"))
    )
    (net (code "39") (name "/GPIO16") (class "Default")
      (node (ref "J1") (pin "19") (pinfunction "19_19") (pintype "passive"))
      (node (ref "U1") (pin "20") (pinfunction "GPIO16/RTC_GPIO16/U0CTS/ADC2_CH5/XTAL_32K_N_20") (pintype "passive"))
    )
    (net (code "40") (name "/GPIO17") (class "Default")
      (node (ref "J1") (pin "20") (pinfunction "20_20") (pintype "passive"))
      (node (ref "U1") (pin "21") (pinfunction "GPIO17/RTC_GPIO17/U1TXD/ADC2_CH6_21") (pintype "passive"))
    )
    (net (code "41") (name "/GPIO18") (class "Default")
      (node (ref "J1") (pin "21") (pinfunction "21_21") (pintype "passive"))
      (node (ref "U1") (pin "22") (pinfunction "GPIO18/RTC_GPIO18/U1RXD/ADC2_CH7/CLK_OUT3_22") (pintype "passive"))
    )
    (net (code "42") (name "/GPIO21") (class "Default")
      (node (ref "J2") (pin "19") (pinfunction "19_19") (pintype "passive"))
      (node (ref "U1") (pin "25") (pinfunction "GPIO21/RTC_GPIO21_25") (pintype "passive"))
    )
    (net (code "43") (name "/GPIO26") (class "Default")
      (node (ref "J2") (pin "18") (pinfunction "18_18") (pintype "passive"))
      (node (ref "U1") (pin "26") (pinfunction "GPIO26/SPICS1_26") (pintype "passive"))
    )
    (net (code "44") (name "/GPIO33") (class "Default")
      (node (ref "J2") (pin "17") (pinfunction "17_17") (pintype "passive"))
      (node (ref "U1") (pin "28") (pinfunction "GPIO33/SPIIO4/FSPIHD/SUBSPIHD_28") (pintype "passive"))
    )
    (net (code "45") (name "/GPIO34") (class "Default")
      (node (ref "J2") (pin "16") (pinfunction "16_16") (pintype "passive"))
      (node (ref "U1") (pin "29") (pinfunction "GPIO34/SPIIO5/FSPICS0/SUBSPICS0_29") (pintype "passive"))
    )
    (net (code "46") (name "/GPIO35") (class "Default")
      (node (ref "J2") (pin "15") (pinfunction "15_15") (pintype "passive"))
      (node (ref "U1") (pin "31") (pinfunction "GPIO35/SPIIO6/FSPID/SUBSPID_31") (pintype "passive"))
    )
    (net (code "47") (name "/GPIO36") (class "Default")
      (node (ref "J2") (pin "14") (pinfunction "14_14") (pintype "passive"))
      (node (ref "U1") (pin "32") (pinfunction "GPIO36/SPIIO7/FSPICLK/SUBSPICLK_32") (pintype "passive"))
    )
    (net (code "48") (name "/GPIO37") (class "Default")
      (node (ref "J2") (pin "13") (pinfunction "13_13") (pintype "passive"))
      (node (ref "U1") (pin "33") (pinfunction "GPIO37/SPIDQS/FSPIQ/SUBSPIQ_33") (pintype "passive"))
    )
    (net (code "49") (name "/GPIO38") (class "Default")
      (node (ref "J2") (pin "12") (pinfunction "12_12") (pintype "passive"))
      (node (ref "U1") (pin "34") (pinfunction "GPIO38/FSPIWP/SUBSPIWP_34") (pintype "passive"))
    )
    (net (code "50") (name "/GPIO39") (class "Default")
      (node (ref "J2") (pin "11") (pinfunction "11_11") (pintype "passive"))
      (node (ref "U1") (pin "35") (pinfunction "MTCK/GPIO39/CLK_OUT3/SUBSPICS1_35") (pintype "passive"))
    )
    (net (code "51") (name "/GPIO40") (class "Default")
      (node (ref "J2") (pin "10") (pinfunction "10_10") (pintype "passive"))
      (node (ref "U1") (pin "36") (pinfunction "MTDO/GPIO40/CLK_OUT2_36") (pintype "passive"))
    )
    (net (code "52") (name "/GPIO41") (class "Default")
      (node (ref "J2") (pin "9") (pinfunction "9_9") (pintype "passive"))
      (node (ref "U1") (pin "37") (pinfunction "MTDI/GPIO41/CLK_OUT1_37") (pintype "passive"))
    )
    (net (code "53") (name "/GPIO42") (class "Default")
      (node (ref "J2") (pin "8") (pinfunction "8_8") (pintype "passive"))
      (node (ref "U1") (pin "38") (pinfunction "MTMS/GPIO42_38") (pintype "passive"))
    )
    (net (code "54") (name "/GPIO45") (class "Default")
      (node (ref "J2") (pin "5") (pinfunction "5_5") (pintype "passive"))
      (node (ref "U1") (pin "41") (pinfunction "GPIO45_41") (pintype "passive"))
    )
    (net (code "55") (name "/GPIO46") (class "Default")
      (node (ref "J2") (pin "4") (pinfunction "4_4") (pintype "passive"))
      (node (ref "U1") (pin "44") (pinfunction "GPIO46_44") (pintype "passive"))
    )
    (net (code "56") (name "/GPIO47") (class "Default")
      (node (ref "J2") (pin "23") (pinfunction "23_23") (pintype "passive"))
      (node (ref "U1") (pin "27") (pinfunction "GPIO47/SPICLK_P_DIFF/SUBSPICLK_P_DIFF_27") (pintype "passive"))
    )
    (net (code "57") (name "/GPIO48") (class "Default")
      (node (ref "J2") (pin "22") (pinfunction "22_22") (pintype "passive"))
      (node (ref "U1") (pin "30") (pinfunction "GPIO48/SPICLK_N_DIFF/SUBSPICLK_N_DIFF_30") (pintype "passive"))
    )
    (net (code "58") (name "/RTS_FTDI") (class "Default")
      (node (ref "Q1") (pin "2") (pinfunction "E_2") (pintype "passive"))
      (node (ref "R18") (pin "1") (pinfunction "1_1") (pintype "passive"))
      (node (ref "U2") (pin "19") (pinfunction "~{RTS}_19") (pintype "passive"))
    )
    (net (code "59") (name "/RXD_FTDI") (class "Default")
      (node (ref "R19") (pin "2") (pinfunction "2_2") (pintype "passive"))
      (node (ref "U2") (pin "1") (pinfunction "RXD_1") (pintype "passive"))
    )
    (net (code "60") (name "/TXD_FTDI") (class "Default")
      (node (ref "R20") (pin "2") (pinfunction "2_2") (pintype "passive"))
      (node (ref "U2") (pin "17") (pinfunction "TXD_17") (pintype "passive"))
    )
    (net (code "61") (name "/U0RXD") (class "Default")
      (node (ref "J2") (pin "6") (pinfunction "6_6") (pintype "passive"))
      (node (ref "R20") (pin "1") (pinfunction "1_1") (pintype "passive"))
      (node (ref "U1") (pin "40") (pinfunction "U0RXD/GPIO44/CLK_OUT2_40") (pintype "passive"))
    )
    (net (code "62") (name "/U0TXD") (class "Default")
      (node (ref "J2") (pin "7") (pinfunction "7_7") (pintype "passive"))
      (node (ref "R19") (pin "1") (pinfunction "1_1") (pintype "passive"))
      (node (ref "U1") (pin "39") (pinfunction "U0TXD/GPIO43/CLK_OUT1_39") (pintype "passive"))
    )
    (net (code "63") (name "/VBUS_SENSE") (class "Default")
      (node (ref "R10") (pin "1") (pinfunction "1_1") (pintype "passive"))
      (node (ref "R13") (pin "1") (pinfunction "1_1") (pintype "passive"))
      (node (ref "U2") (pin "16") (pinfunction "CBUS3_16") (pintype "passive"))
    )
    (net (code "64") (name "GND") (class "Default")
      (node (ref "C1") (pin "1") (pinfunction "1_1") (pintype "passive"))
      (node (ref "C10") (pin "1") (pinfunction "1_1") (pintype "passive"))
      (node (ref "C11") (pin "1") (pinfunction "1_1") (pintype "passive"))
      (node (ref "C12") (pin "1") (pinfunction "1_1") (pintype "passive"))
      (node (ref "C13") (pin "1") (pinfunction "1_1") (pintype "passive"))
      (node (ref "C14") (pin "1") (pinfunction "1_1") (pintype "passive"))
      (node (ref "C15") (pin "1") (pinfunction "1_1") (pintype "passive"))
      (node (ref "C16") (pin "1") (pinfunction "1_1") (pintype "passive"))
      (node (ref "C17") (pin "1") (pinfunction "1_1") (pintype "passive"))
      (node (ref "C2") (pin "1") (pinfunction "1_1") (pintype "passive"))
      (node (ref "C3") (pin "1") (pinfunction "1_1") (pintype "passive"))
      (node (ref "C4") (pin "1") (pinfunction "1_1") (pintype "passive"))
      (node (ref "C5") (pin "1") (pinfunction "1_1") (pintype "passive"))
      (node (ref "C6") (pin "1") (pinfunction "1_1") (pintype "passive"))
      (node (ref "C7") (pin "1") (pinfunction "1_1") (pintype "passive"))
      (node (ref "C8") (pin "1") (pinfunction "1_1") (pintype "passive"))
      (node (ref "C9") (pin "1") (pinfunction "1_1") (pintype "passive"))
      (node (ref "D1") (pin "1") (pinfunction "1_1") (pintype "passive"))
      (node (ref "D3") (pin "1") (pinfunction "1_1") (pintype "passive"))
      (node (ref "D4") (pin "1") (pinfunction "1_1") (pintype "passive"))
      (node (ref "D5") (pin "1") (pinfunction "1_1") (pintype "passive"))
      (node (ref "D6") (pin "1") (pinfunction "1_1") (pintype "passive"))
      (node (ref "D7") (pin "1") (pinfunction "1_1") (pintype "passive"))
      (node (ref "D8") (pin "1") (pinfunction "1_1") (pintype "passive"))
      (node (ref "J1") (pin "1") (pinfunction "1_1") (pintype "passive"))
      (node (ref "J1") (pin "23") (pinfunction "23_23") (pintype "passive"))
      (node (ref "J2") (pin "2") (pinfunction "2_2") (pintype "passive"))
      (node (ref "J2") (pin "24") (pinfunction "24_24") (pintype "passive"))
      (node (ref "J3") (pin "A1B12") (pinfunction "GND_A1B12_A1B12") (pintype "passive"))
      (node (ref "J3") (pin "B1A12") (pinfunction "GND_B1A12_B1A12") (pintype "passive"))
      (node (ref "J3") (pin "S1") (pinfunction "SHIELD_1_S1") (pintype "passive"))
      (node (ref "J3") (pin "S2") (pinfunction "SHIELD_2_S2") (pintype "passive"))
      (node (ref "J3") (pin "S3") (pinfunction "SHIELD_3_S3") (pintype "passive"))
      (node (ref "J3") (pin "S4") (pinfunction "SHIELD_4_S4") (pintype "passive"))
      (node (ref "J4") (pin "A1B12") (pinfunction "GND_A1B12_A1B12") (pintype "passive"))
      (node (ref "J4") (pin "B1A12") (pinfunction "GND_B1A12_B1A12") (pintype "passive"))
      (node (ref "J4") (pin "S1") (pinfunction "SHIELD_1_S1") (pintype "passive"))
      (node (ref "J4") (pin "S2") (pinfunction "SHIELD_2_S2") (pintype "passive"))
      (node (ref "J4") (pin "S3") (pinfunction "SHIELD_3_S3") (pintype "passive"))
      (node (ref "J4") (pin "S4") (pinfunction "SHIELD_4_S4") (pintype "passive"))
      (node (ref "R11") (pin "1") (pinfunction "1_1") (pintype "passive"))
      (node (ref "R12") (pin "1") (pinfunction "1_1") (pintype "passive"))
      (node (ref "R13") (pin "2") (pinfunction "2_2") (pintype "passive"))
      (node (ref "R14") (pin "1") (pinfunction "1_1") (pintype "passive"))
      (node (ref "R15") (pin "1") (pinfunction "1_1") (pintype "passive"))
      (node (ref "R9") (pin "2") (pinfunction "2_2") (pintype "passive"))
      (node (ref "SW1") (pin "3") (pinfunction "3_3") (pintype "passive"))
      (node (ref "SW1") (pin "4") (pinfunction "4_4") (pintype "passive"))
      (node (ref "SW2") (pin "3") (pinfunction "3_3") (pintype "passive"))
      (node (ref "SW2") (pin "4") (pinfunction "4_4") (pintype "passive"))
      (node (ref "U1") (pin "1") (pinfunction "GND_01_1") (pintype "passive"))
      (node (ref "U1") (pin "2") (pinfunction "GND_02_2") (pintype "passive"))
      (node (ref "U1") (pin "42") (pinfunction "GND_42") (pintype "passive"))
      (node (ref "U1") (pin "43") (pinfunction "GND_43") (pintype "passive"))
      (node (ref "U1") (pin "46") (pinfunction "GND_46_46") (pintype "passive"))
      (node (ref "U1") (pin "47") (pinfunction "GND_47_47") (pintype "passive"))
      (node (ref "U1") (pin "48") (pinfunction "GND_48_48") (pintype "passive"))
      (node (ref "U1") (pin "49") (pinfunction "GND_49_49") (pintype "passive"))
      (node (ref "U1") (pin "50") (pinfunction "GND_50_50") (pintype "passive"))
      (node (ref "U1") (pin "51") (pinfunction "GND_51_51") (pintype "passive"))
      (node (ref "U1") (pin "52") (pinfunction "GND_52_52") (pintype "passive"))
      (node (ref "U1") (pin "53") (pinfunction "GND_53_53") (pintype "passive"))
      (node (ref "U1") (pin "54") (pinfunction "GND_54_54") (pintype "passive"))
      (node (ref "U1") (pin "55") (pinfunction "GND_55_55") (pintype "passive"))
      (node (ref "U1") (pin "56") (pinfunction "GND_56_56") (pintype "passive"))
      (node (ref "U1") (pin "57") (pinfunction "GND_57_57") (pintype "passive"))
      (node (ref "U1") (pin "58") (pinfunction "GND_58_58") (pintype "passive"))
      (node (ref "U1") (pin "59") (pinfunction "GND_59_59") (pintype "passive"))
      (node (ref "U1") (pin "60") (pinfunction "GND_60_60") (pintype "passive"))
      (node (ref "U1") (pin "61") (pinfunction "GND_61_61") (pintype "passive"))
      (node (ref "U1") (pin "62") (pinfunction "GND_62_62") (pintype "passive"))
      (node (ref "U1") (pin "63") (pinfunction "GND_63_63") (pintype "passive"))
      (node (ref "U1") (pin "64") (pinfunction "GND_64_64") (pintype "passive"))
      (node (ref "U1") (pin "65") (pinfunction "GND_65_65") (pintype "passive"))
      (node (ref "U1") (pin "66") (pinfunction "GND_66_66") (pintype "passive"))
      (node (ref "U1") (pin "67") (pinfunction "GND_67_67") (pintype "passive"))
      (node (ref "U1") (pin "68") (pinfunction "GND_68_68") (pintype "passive"))
      (node (ref "U1") (pin "69") (pinfunction "GND_69_69") (pintype "passive"))
      (node (ref "U1") (pin "70") (pinfunction "GND_70_70") (pintype "passive"))
      (node (ref "U1") (pin "71") (pinfunction "GND_71_71") (pintype "passive"))
      (node (ref "U1") (pin "72") (pinfunction "GND_72_72") (pintype "passive"))
      (node (ref "U1") (pin "73") (pinfunction "GND_73_73") (pintype "passive"))
      (node (ref "U2") (pin "13") (pinfunction "GND_13") (pintype "passive"))
      (node (ref "U2") (pin "21") (pinfunction "GND_21") (pintype "passive"))
      (node (ref "U2") (pin "3") (pinfunction "GND_3") (pintype "passive"))
      (node (ref "U3") (pin "2") (pinfunction "GND_2") (pintype "power_in"))
      (node (ref "U3") (pin "4") (pinfunction "GND_4") (pintype "power_in"))
    )
    (net (code "65") (name "Net-(D1-Pad2)") (class "Default")
      (node (ref "D1") (pin "2") (pinfunction "2_2") (pintype "passive"))
      (node (ref "R3") (pin "1") (pinfunction "1_1") (pintype "passive"))
    )
    (net (code "66") (name "Net-(D2-Pad2)") (class "Default")
      (node (ref "D2") (pin "2") (pinfunction "2_2") (pintype "passive"))
      (node (ref "R4") (pin "1") (pinfunction "1_1") (pintype "passive"))
    )
    (net (code "67") (name "Net-(J3-CC1)") (class "Default")
      (node (ref "J3") (pin "A5") (pinfunction "CC1_A5") (pintype "passive"))
      (node (ref "R12") (pin "2") (pinfunction "2_2") (pintype "passive"))
    )
    (net (code "68") (name "Net-(J3-CC2)") (class "Default")
      (node (ref "J3") (pin "B5") (pinfunction "CC2_B5") (pintype "passive"))
      (node (ref "R11") (pin "2") (pinfunction "2_2") (pintype "passive"))
    )
    (net (code "69") (name "Net-(J4-CC1)") (class "Default")
      (node (ref "J4") (pin "A5") (pinfunction "CC1_A5") (pintype "passive"))
      (node (ref "R15") (pin "2") (pinfunction "2_2") (pintype "passive"))
    )
    (net (code "70") (name "Net-(J4-CC2)") (class "Default")
      (node (ref "J4") (pin "B5") (pinfunction "CC2_B5") (pintype "passive"))
      (node (ref "R14") (pin "2") (pinfunction "2_2") (pintype "passive"))
    )
    (net (code "71") (name "Net-(Q1-B)") (class "Default")
      (node (ref "Q1") (pin "1") (pinfunction "B_1") (pintype "passive"))
      (node (ref "R16") (pin "2") (pinfunction "2_2") (pintype "passive"))
    )
    (net (code "72") (name "Net-(Q2-B)") (class "Default")
      (node (ref "Q2") (pin "1") (pinfunction "B_1") (pintype "passive"))
      (node (ref "R18") (pin "2") (pinfunction "2_2") (pintype "passive"))
    )
    (net (code "73") (name "Net-(U2-CBUS0)") (class "Default")
      (node (ref "R9") (pin "1") (pinfunction "1_1") (pintype "passive"))
      (node (ref "U2") (pin "15") (pinfunction "CBUS0_15") (pintype "passive"))
    )
    (net (code "74") (name "unconnected-(J1-Pad24)") (class "Default")
      (node (ref "J1") (pin "24") (pinfunction "24_24") (pintype "passive+no_connect"))
    )
    (net (code "75") (name "unconnected-(J3-SBU1-PadA8)") (class "Default")
      (node (ref "J3") (pin "A8") (pinfunction "SBU1_A8") (pintype "passive+no_connect"))
    )
    (net (code "76") (name "unconnected-(J3-SBU2-PadB8)") (class "Default")
      (node (ref "J3") (pin "B8") (pinfunction "SBU2_B8") (pintype "passive+no_connect"))
    )
    (net (code "77") (name "unconnected-(J4-SBU1-PadA8)") (class "Default")
      (node (ref "J4") (pin "A8") (pinfunction "SBU1_A8") (pintype "passive+no_connect"))
    )
    (net (code "78") (name "unconnected-(J4-SBU2-PadB8)") (class "Default")
      (node (ref "J4") (pin "B8") (pinfunction "SBU2_B8") (pintype "passive+no_connect"))
    )
    (net (code "79") (name "unconnected-(U2-CBUS1-Pad14)") (class "Default")
      (node (ref "U2") (pin "14") (pinfunction "CBUS1_14") (pintype "passive+no_connect"))
    )
    (net (code "80") (name "unconnected-(U2-CBUS2-Pad7)") (class "Default")
      (node (ref "U2") (pin "7") (pinfunction "CBUS2_7") (pintype "passive+no_connect"))
    )
    (net (code "81") (name "unconnected-(U2-~{CTS}-Pad6)") (class "Default")
      (node (ref "U2") (pin "6") (pinfunction "~{CTS}_6") (pintype "passive+no_connect"))
    )
    (net (code "82") (name "unconnected-(U2-~{DCD}-Pad5)") (class "Default")
      (node (ref "U2") (pin "5") (pinfunction "~{DCD}_5") (pintype "passive+no_connect"))
    )
    (net (code "83") (name "unconnected-(U2-~{DSR}-Pad4)") (class "Default")
      (node (ref "U2") (pin "4") (pinfunction "~{DSR}_4") (pintype "passive+no_connect"))
    )
    (net (code "84") (name "unconnected-(U2-~{RI}-Pad2)") (class "Default")
      (node (ref "U2") (pin "2") (pinfunction "~{RI}_2") (pintype "passive+no_connect"))
    )
  )
)
